# MagneticPowerSwitch.net
KiCad netlist of a schematic drawn in Altium Designer
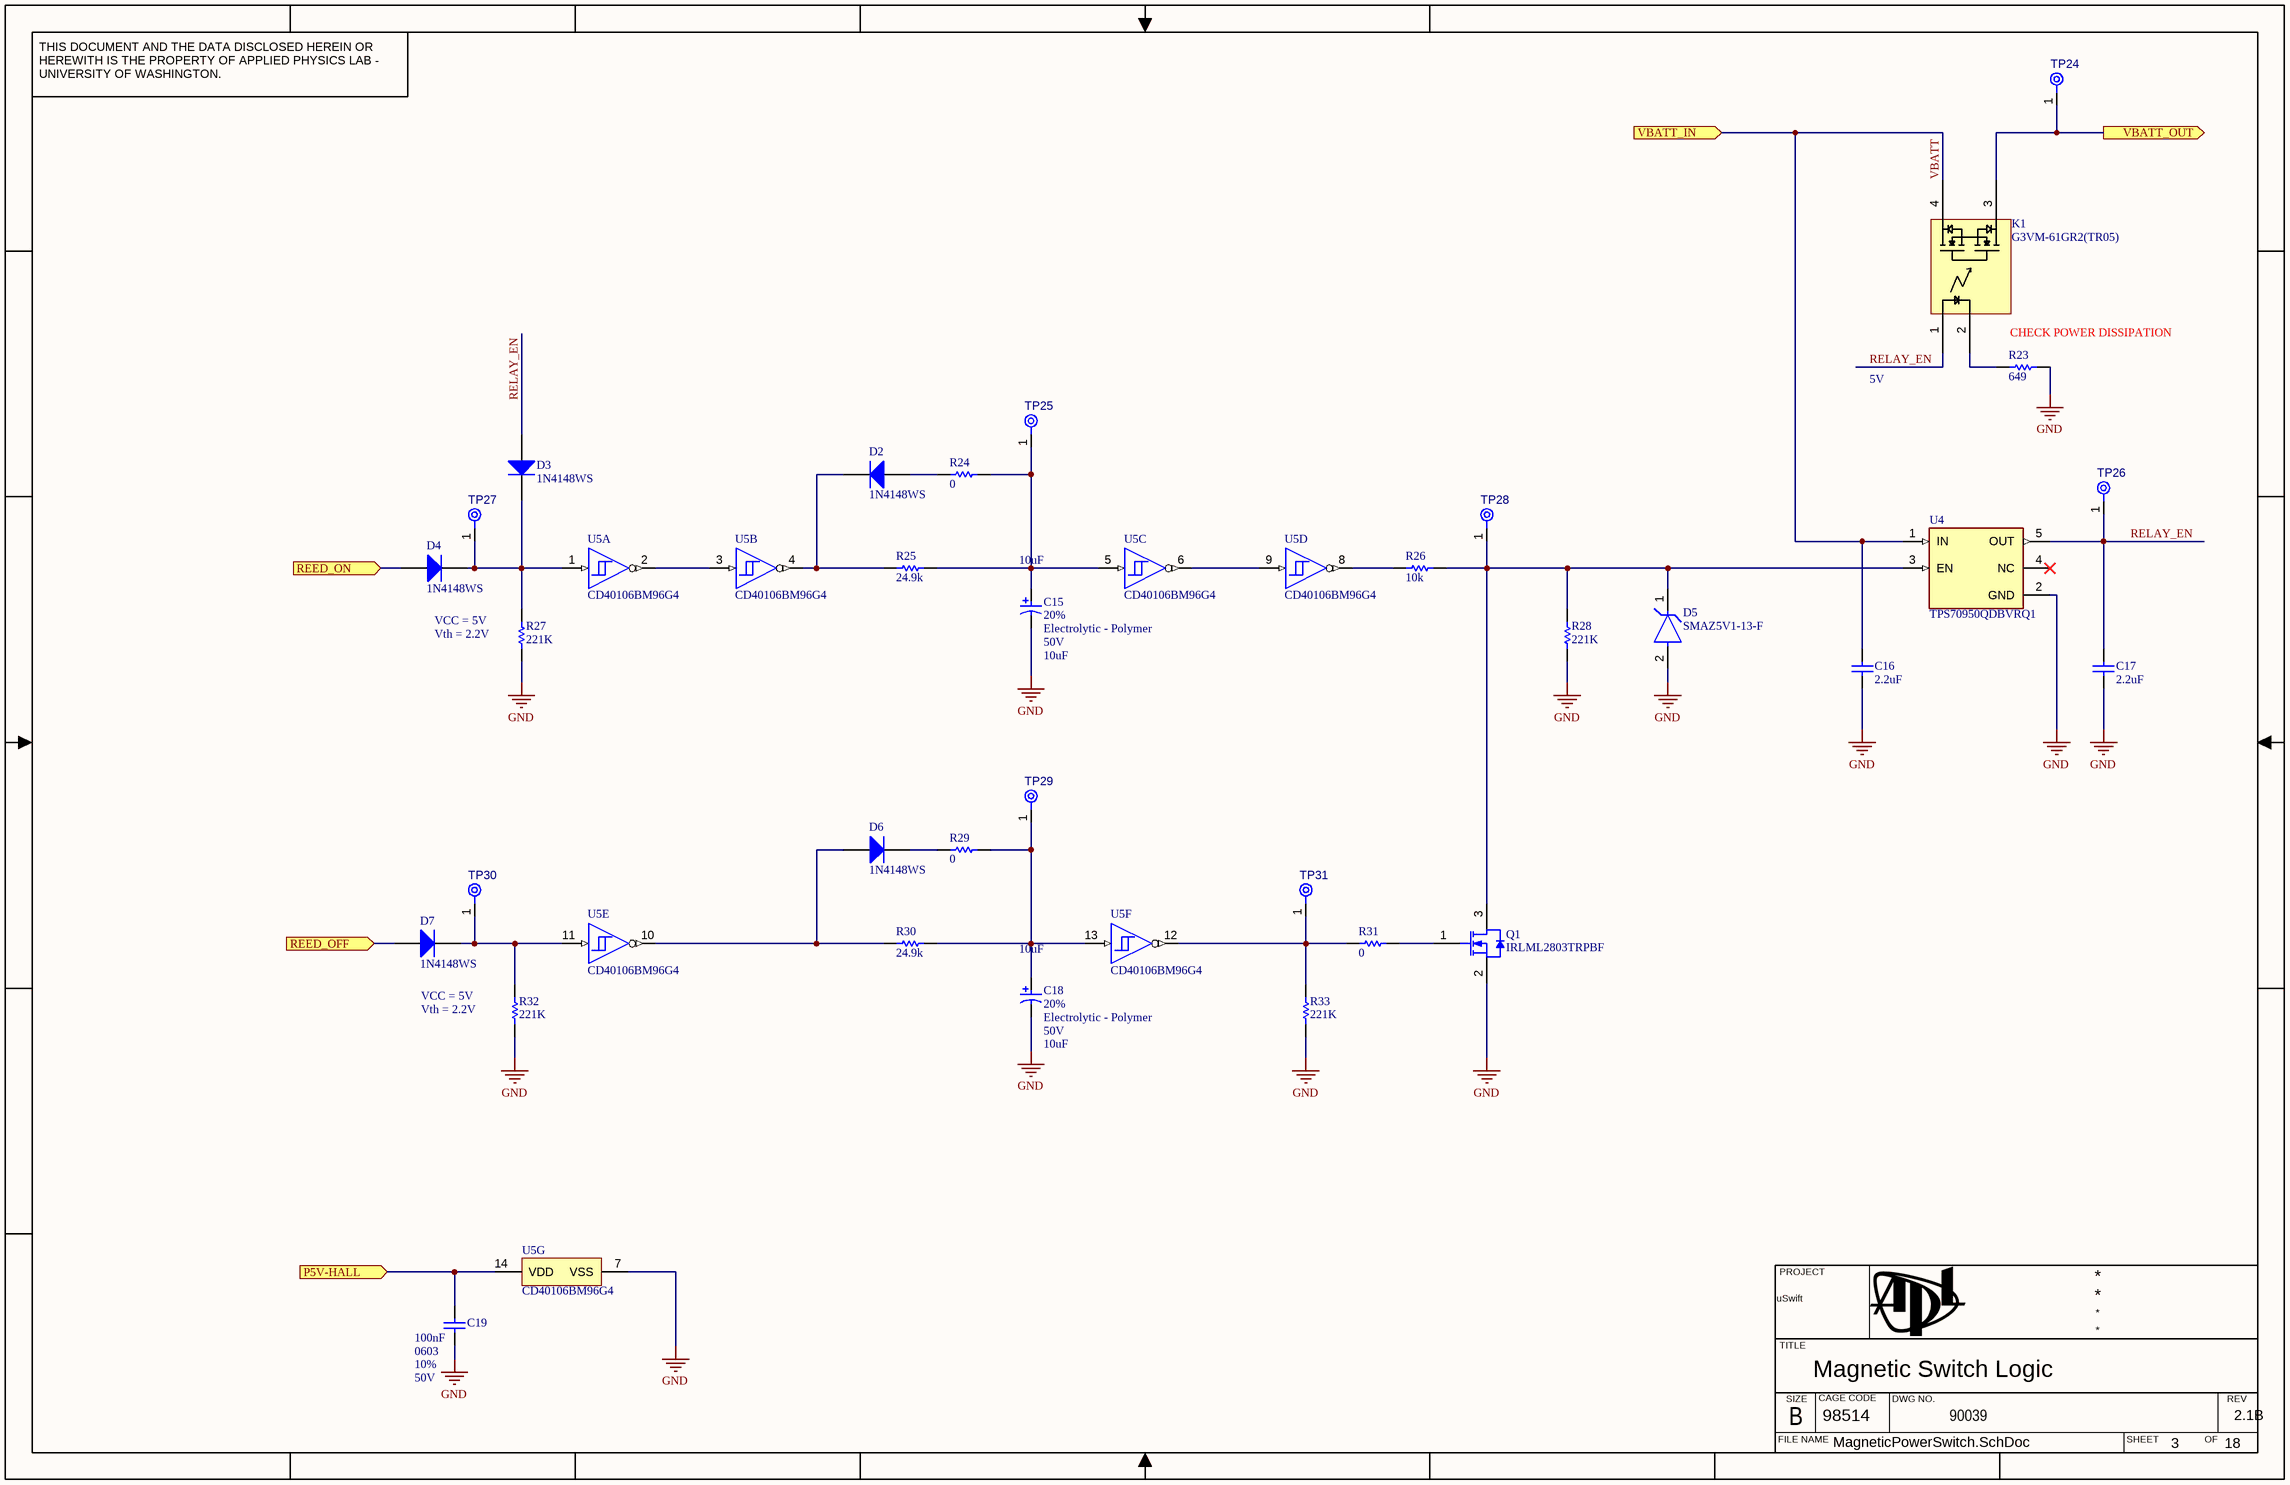
[diagram p0: MagneticPowerSwitch.SchDoc]

(export (version "E")
  (design (tool "Eeschema 10.0.6"))
  (components
    (comp (ref "C15")
      (value "10uF")
      (footprint "CAPAE5953X61M")
      (description "Cap Aluminum 10uF 50V 20% (5 X 5.8mm) SMD 0.12 Ohm 750mA 5000 hr 105°C Embossed T/R")
      (fields
        (field (name "TOLERANCE") "20%")
        (field (name "MATERIAL") "Electrolytic - Polymer")
        (field (name "MANUFACTURER") "Panasonic")
        (field (name "VOLTAGE RATING") "50V")
        (field (name "CAPACITANCE") "10uF")
        (field (name "PART NUMBER") "EEH-ZA1H100R")
      )
      (libsource (lib "Applied Physics Lab") (part "CAP-P-2"))
    )
    (comp (ref "C16")
      (value "2.2uF")
      (footprint "CAPC3225X270X30ML30")
      (description "Chip Capacitor, 2.2uF, 10%, 50 V, X7R 1210 (3225 Metric)")
      (fields (field (name "TOLERANCE") "10%") (field (name "Comment") "Capacitor 2.2uF 10%, 50V, X7R, 1210"))
      (libsource (lib "Applied Physics Lab") (part "CAP-NP-2"))
    )
    (comp (ref "C17")
      (value "2.2uF")
      (footprint "CAPC3225X270X30ML30")
      (description "Chip Capacitor, 2.2uF, 10%, 50 V, X7R 1210 (3225 Metric)")
      (fields (field (name "TOLERANCE") "10%") (field (name "Comment") "Capacitor 2.2uF 10%, 50V, X7R, 1210"))
      (libsource (lib "Applied Physics Lab") (part "CAP-NP-2"))
    )
    (comp (ref "C18")
      (value "10uF")
      (footprint "CAPAE5953X61M")
      (description "Cap Aluminum 10uF 50V 20% (5 X 5.8mm) SMD 0.12 Ohm 750mA 5000 hr 105°C Embossed T/R")
      (fields
        (field (name "TOLERANCE") "20%")
        (field (name "MATERIAL") "Electrolytic - Polymer")
        (field (name "MANUFACTURER") "Panasonic")
        (field (name "VOLTAGE RATING") "50V")
        (field (name "CAPACITANCE") "10uF")
        (field (name "PART NUMBER") "EEH-ZA1H100R")
      )
      (libsource (lib "Applied Physics Lab") (part "CAP-P-2"))
    )
    (comp (ref "C19")
      (value "100nF")
      (footprint "CAPC1608X90X40ML10T20")
      (description "Chip Capacitor, 100nF, +/- 10%, 50 V, X7R 0603 (1608 Metric)")
      (fields
        (field (name "CASE/PACKAGE") "0603")
        (field (name "TOLERANCE") "10%")
        (field (name "VOLTAGE RATING") "50V")
        (field (name "Comment") "Capacitor 100nF +/- 10%, 50V, X7R, 0603")
      )
      (libsource (lib "Applied Physics Lab") (part "CAP-NP-2"))
    )
    (comp (ref "D2")
      (value "1N4148WS")
      (footprint "FAIR-SOD-323_V")
      (description "Small Signal Diode, 75 V, 0.15 A, -55 to 150 degC, 2-Pin SOD-323, RoHS, Tape and Reel")
      (fields (field (name "MANUFACTURER") "Fairchild"))
      (libsource (lib "Applied Physics Lab") (part "D-AK-2"))
    )
    (comp (ref "D3")
      (value "1N4148WS")
      (footprint "FAIR-SOD-323_V")
      (description "Small Signal Diode, 75 V, 0.15 A, -55 to 150 degC, 2-Pin SOD-323, RoHS, Tape and Reel")
      (fields (field (name "MANUFACTURER") "Fairchild"))
      (libsource (lib "Applied Physics Lab") (part "D-AK-2"))
    )
    (comp (ref "D4")
      (value "1N4148WS")
      (footprint "FAIR-SOD-323_V")
      (description "Small Signal Diode, 75 V, 0.15 A, -55 to 150 degC, 2-Pin SOD-323, RoHS, Tape and Reel")
      (fields (field (name "MANUFACTURER") "Fairchild"))
      (libsource (lib "Applied Physics Lab") (part "D-AK-2"))
    )
    (comp (ref "D5")
      (value "SMAZ5V1-13-F")
      (footprint "FP-SMA-MFG")
      (description "Vz=5.1V 4.84V~5.4V Izt=100mA P=1W")
      (fields (field (name "TOLERANCE") "5%"))
      (libsource (lib "Applied Physics Lab") (part "f813f71cba58e380607f5dd3caf9714"))
    )
    (comp (ref "D6")
      (value "1N4148WS")
      (footprint "FAIR-SOD-323_V")
      (description "Small Signal Diode, 75 V, 0.15 A, -55 to 150 degC, 2-Pin SOD-323, RoHS, Tape and Reel")
      (fields (field (name "MANUFACTURER") "Fairchild"))
      (libsource (lib "Applied Physics Lab") (part "D-AK-2"))
    )
    (comp (ref "D7")
      (value "1N4148WS")
      (footprint "FAIR-SOD-323_V")
      (description "Small Signal Diode, 75 V, 0.15 A, -55 to 150 degC, 2-Pin SOD-323, RoHS, Tape and Reel")
      (fields (field (name "MANUFACTURER") "Fairchild"))
      (libsource (lib "Applied Physics Lab") (part "D-AK-2"))
    )
    (comp (ref "K1")
      (value "G3VM-61GR2(TR05)")
      (footprint "G3VM-61GR2(TR05)-Footprint-1")
      (description "Relay Ssr 25MA 1.48V Dc-in 1.3A 48V Ac/dc-out 4-PIN Sop T/r")
      (libsource (lib "Applied Physics Lab") (part "G3VM-Symbol-1"))
    )
    (comp (ref "Q1")
      (value "IRLML2803TRPBF")
      (footprint "SOT95P237X112-3M")
      (description "Mosfet, Power; N-ch; Vdss 30V; Rds(on) 0.25 Ohm; Id 1.2A; MICRO3; Pd 540MW; Vgs +/-20V")
      (fields (field (name "MANUFACTURER") "International Rectifier"))
      (libsource (lib "Applied Physics Lab") (part "NEMOS-GSD-3"))
    )
    (comp (ref "R23")
      (value "649")
      (footprint "RESC1609X50X30ML08T20")
      (description "Chip Resistor, 649 Ohm, +/- 1%, 0.1 W, -55 to 155 degC, 0603 (1608 Metric)")
      (fields (field (name "POWER") "100mW") (field (name "TOLERANCE") "1%"))
      (libsource (lib "Applied Physics Lab") (part "RES-2"))
    )
    (comp (ref "R24")
      (value "0")
      (footprint "RESC1608X55X25ML10T15")
      (description "Chip Resistor, 0 Ohm, 0.1 W, -55 to 155 degC, 0603 (1608 Metric)")
      (fields (field (name "TOLERANCE") "5%") (field (name "POWER") "100mW"))
      (libsource (lib "Applied Physics Lab") (part "RES-2"))
    )
    (comp (ref "R25")
      (value "24.9k")
      (footprint "RESC1608X55X25ML10T15")
      (description "Chip Resistor, 24.9k Ohm, +/- 1%, 0.1 W, -55 to 155 degC, 0603 (1608 Metric)")
      (fields (field (name "TOLERANCE") "1%") (field (name "POWER") "100mW"))
      (libsource (lib "Applied Physics Lab") (part "RES-2"))
    )
    (comp (ref "R26")
      (value "10k")
      (footprint "RESC1608X55X25ML10T15")
      (description "Chip Resistor, 10 KOhm, +/- 1%, 01 W, -55 to 155 degC, 0603 (1608 Metric)")
      (fields (field (name "TOLERANCE") "1%") (field (name "POWER") "100mW"))
      (libsource (lib "Applied Physics Lab") (part "RES-2"))
    )
    (comp (ref "R27")
      (value "221K")
      (footprint "RESC1609X50X30ML08T20")
      (description "Chip Resistor, 221k Ohm, +/- 1%, 0.1 W, -55 to 155 degC, 0603 (1608 Metric)")
      (fields (field (name "TOLERANCE") "1%") (field (name "POWER") "100mW"))
      (libsource (lib "Applied Physics Lab") (part "RES-2"))
    )
    (comp (ref "R28")
      (value "221K")
      (footprint "RESC1609X50X30ML08T20")
      (description "Chip Resistor, 221k Ohm, +/- 1%, 0.1 W, -55 to 155 degC, 0603 (1608 Metric)")
      (fields (field (name "TOLERANCE") "1%") (field (name "POWER") "100mW"))
      (libsource (lib "Applied Physics Lab") (part "RES-2"))
    )
    (comp (ref "R29")
      (value "0")
      (footprint "RESC1608X55X25ML10T15")
      (description "Chip Resistor, 0 Ohm, 0.1 W, -55 to 155 degC, 0603 (1608 Metric)")
      (fields (field (name "TOLERANCE") "5%") (field (name "POWER") "100mW"))
      (libsource (lib "Applied Physics Lab") (part "RES-2"))
    )
    (comp (ref "R30")
      (value "24.9k")
      (footprint "RESC1608X55X25ML10T15")
      (description "Chip Resistor, 24.9k Ohm, +/- 1%, 0.1 W, -55 to 155 degC, 0603 (1608 Metric)")
      (fields (field (name "TOLERANCE") "1%") (field (name "POWER") "100mW"))
      (libsource (lib "Applied Physics Lab") (part "RES-2"))
    )
    (comp (ref "R31")
      (value "0")
      (footprint "RESC1608X55X25ML10T15")
      (description "Chip Resistor, 0 Ohm, 0.1 W, -55 to 155 degC, 0603 (1608 Metric)")
      (fields (field (name "TOLERANCE") "5%") (field (name "POWER") "100mW"))
      (libsource (lib "Applied Physics Lab") (part "RES-2"))
    )
    (comp (ref "R32")
      (value "221K")
      (footprint "RESC1609X50X30ML08T20")
      (description "Chip Resistor, 221k Ohm, +/- 1%, 0.1 W, -55 to 155 degC, 0603 (1608 Metric)")
      (fields (field (name "TOLERANCE") "1%") (field (name "POWER") "100mW"))
      (libsource (lib "Applied Physics Lab") (part "RES-2"))
    )
    (comp (ref "R33")
      (value "221K")
      (footprint "RESC1609X50X30ML08T20")
      (description "Chip Resistor, 221k Ohm, +/- 1%, 0.1 W, -55 to 155 degC, 0603 (1608 Metric)")
      (fields (field (name "TOLERANCE") "1%") (field (name "POWER") "100mW"))
      (libsource (lib "Applied Physics Lab") (part "RES-2"))
    )
    (comp (ref "TP24")
      (value "TPAD6R-CIRCLED")
      (footprint "TP06R - Circled")
      (description "0.6mm round with a silkscreen circle.")
      (libsource (lib "Applied Physics Lab") (part "CMP-001-0001-4"))
    )
    (comp (ref "TP25")
      (value "TPAD6R-CIRCLED")
      (footprint "TP06R - Circled")
      (description "0.6mm round with a silkscreen circle.")
      (libsource (lib "Applied Physics Lab") (part "CMP-001-0001-4"))
    )
    (comp (ref "TP26")
      (value "TPAD6R-CIRCLED")
      (footprint "TP06R - Circled")
      (description "0.6mm round with a silkscreen circle.")
      (libsource (lib "Applied Physics Lab") (part "CMP-001-0001-4"))
    )
    (comp (ref "TP27")
      (value "TPAD6R-CIRCLED")
      (footprint "TP06R - Circled")
      (description "0.6mm round with a silkscreen circle.")
      (libsource (lib "Applied Physics Lab") (part "CMP-001-0001-4"))
    )
    (comp (ref "TP28")
      (value "TPAD6R-CIRCLED")
      (footprint "TP06R - Circled")
      (description "0.6mm round with a silkscreen circle.")
      (libsource (lib "Applied Physics Lab") (part "CMP-001-0001-4"))
    )
    (comp (ref "TP29")
      (value "TPAD6R-CIRCLED")
      (footprint "TP06R - Circled")
      (description "0.6mm round with a silkscreen circle.")
      (libsource (lib "Applied Physics Lab") (part "CMP-001-0001-4"))
    )
    (comp (ref "TP30")
      (value "TPAD6R-CIRCLED")
      (footprint "TP06R - Circled")
      (description "0.6mm round with a silkscreen circle.")
      (libsource (lib "Applied Physics Lab") (part "CMP-001-0001-4"))
    )
    (comp (ref "TP31")
      (value "TPAD6R-CIRCLED")
      (footprint "TP06R - Circled")
      (description "0.6mm round with a silkscreen circle.")
      (libsource (lib "Applied Physics Lab") (part "CMP-001-0001-4"))
    )
    (comp (ref "U4")
      (value "TPS70950QDBVRQ1")
      (footprint "FP-DBV0005A-IPC_A")
      (description "LDO Regulator Pos 5V 0.15A 5-Pin SOT-23 T/R")
      (libsource (lib "Applied Physics Lab") (part "030fc2a58bb2cf79005932a3da0ea32"))
    )
    (comp (ref "U5")
      (value "CD40106BM96G4")
      (footprint "D0014A_M")
      (description "6-ch, 3-V to 18-V inverters with Schmitt-Trigger inputs 14-SOIC -55 to 125")
      (libsource (lib "Applied Physics Lab") (part "TI-CD40XXXB-14-SCHMITT"))
    )
  )
  (nets
    (net (code "1") (name "/P5V-HALL") (class "Default")
      (node (ref "C19") (pin "2") (pinfunction "2_2") (pintype "passive"))
      (node (ref "U5") (pin "14") (pinfunction "VDD_14") (pintype "power_in"))
    )
    (net (code "2") (name "/REED_OFF") (class "Default")
      (node (ref "D7") (pin "1") (pinfunction "A_1") (pintype "passive"))
    )
    (net (code "3") (name "/REED_ON") (class "Default")
      (node (ref "D4") (pin "1") (pinfunction "A_1") (pintype "passive"))
    )
    (net (code "4") (name "/RELAY_EN") (class "Default")
      (node (ref "C17") (pin "2") (pinfunction "2_2") (pintype "passive"))
      (node (ref "D3") (pin "1") (pinfunction "A_1") (pintype "passive"))
      (node (ref "K1") (pin "1") (pinfunction "+_CNTL_1") (pintype "passive"))
      (node (ref "TP26") (pin "1") (pinfunction "TP_1") (pintype "passive"))
      (node (ref "U4") (pin "5") (pinfunction "OUT_5") (pintype "output"))
    )
    (net (code "5") (name "/VBATT") (class "Default")
      (node (ref "C16") (pin "2") (pinfunction "2_2") (pintype "passive"))
      (node (ref "K1") (pin "4") (pinfunction "DRAIN_4") (pintype "passive"))
      (node (ref "U4") (pin "1") (pinfunction "IN_1") (pintype "input"))
    )
    (net (code "6") (name "/VBATT_OUT") (class "Default")
      (node (ref "K1") (pin "3") (pinfunction "DRAIN_3") (pintype "passive"))
      (node (ref "TP24") (pin "1") (pinfunction "TP_1") (pintype "passive"))
    )
    (net (code "7") (name "GND") (class "Default")
      (node (ref "C15") (pin "2") (pinfunction "2_2") (pintype "passive"))
      (node (ref "C16") (pin "1") (pinfunction "1_1") (pintype "passive"))
      (node (ref "C17") (pin "1") (pinfunction "1_1") (pintype "passive"))
      (node (ref "C18") (pin "2") (pinfunction "2_2") (pintype "passive"))
      (node (ref "C19") (pin "1") (pinfunction "1_1") (pintype "passive"))
      (node (ref "D5") (pin "2") (pinfunction "A_2") (pintype "passive"))
      (node (ref "Q1") (pin "2") (pinfunction "S_2") (pintype "passive"))
      (node (ref "R23") (pin "1") (pinfunction "1_1") (pintype "passive"))
      (node (ref "R27") (pin "1") (pinfunction "1_1") (pintype "passive"))
      (node (ref "R28") (pin "1") (pinfunction "1_1") (pintype "passive"))
      (node (ref "R32") (pin "1") (pinfunction "1_1") (pintype "passive"))
      (node (ref "R33") (pin "1") (pinfunction "1_1") (pintype "passive"))
      (node (ref "U4") (pin "2") (pinfunction "GND_2") (pintype "power_in"))
      (node (ref "U5") (pin "7") (pinfunction "VSS_7") (pintype "power_in"))
    )
    (net (code "8") (name "Net-(D2-A)") (class "Default")
      (node (ref "D2") (pin "1") (pinfunction "A_1") (pintype "passive"))
      (node (ref "R24") (pin "1") (pinfunction "1_1") (pintype "passive"))
    )
    (net (code "9") (name "Net-(D2-K)") (class "Default")
      (node (ref "D2") (pin "2") (pinfunction "K_2") (pintype "passive"))
      (node (ref "R25") (pin "1") (pinfunction "1_1") (pintype "passive"))
      (node (ref "U5") (pin "4") (pinfunction "H=~{B}_4") (pintype "output"))
    )
    (net (code "10") (name "Net-(D3-K)") (class "Default")
      (node (ref "D3") (pin "2") (pinfunction "K_2") (pintype "passive"))
      (node (ref "D4") (pin "2") (pinfunction "K_2") (pintype "passive"))
      (node (ref "R27") (pin "2") (pinfunction "2_2") (pintype "passive"))
      (node (ref "TP27") (pin "1") (pinfunction "TP_1") (pintype "passive"))
      (node (ref "U5") (pin "1") (pinfunction "A_1") (pintype "input"))
    )
    (net (code "11") (name "Net-(D5-C)") (class "Default")
      (node (ref "D5") (pin "1") (pinfunction "C_1") (pintype "passive"))
      (node (ref "Q1") (pin "3") (pinfunction "D_3") (pintype "passive"))
      (node (ref "R26") (pin "2") (pinfunction "2_2") (pintype "passive"))
      (node (ref "R28") (pin "2") (pinfunction "2_2") (pintype "passive"))
      (node (ref "TP28") (pin "1") (pinfunction "TP_1") (pintype "passive"))
      (node (ref "U4") (pin "3") (pinfunction "EN_3") (pintype "input"))
    )
    (net (code "12") (name "Net-(D6-A)") (class "Default")
      (node (ref "D6") (pin "1") (pinfunction "A_1") (pintype "passive"))
      (node (ref "R30") (pin "1") (pinfunction "1_1") (pintype "passive"))
      (node (ref "U5") (pin "10") (pinfunction "K=~{E}_10") (pintype "output"))
    )
    (net (code "13") (name "Net-(D6-K)") (class "Default")
      (node (ref "D6") (pin "2") (pinfunction "K_2") (pintype "passive"))
      (node (ref "R29") (pin "1") (pinfunction "1_1") (pintype "passive"))
    )
    (net (code "14") (name "Net-(D7-K)") (class "Default")
      (node (ref "D7") (pin "2") (pinfunction "K_2") (pintype "passive"))
      (node (ref "R32") (pin "2") (pinfunction "2_2") (pintype "passive"))
      (node (ref "TP30") (pin "1") (pinfunction "TP_1") (pintype "passive"))
      (node (ref "U5") (pin "11") (pinfunction "E_11") (pintype "input"))
    )
    (net (code "15") (name "Net-(K1--_CNTL)") (class "Default")
      (node (ref "K1") (pin "2") (pinfunction "-_CNTL_2") (pintype "passive"))
      (node (ref "R23") (pin "2") (pinfunction "2_2") (pintype "passive"))
    )
    (net (code "16") (name "Net-(Q1-G)") (class "Default")
      (node (ref "Q1") (pin "1") (pinfunction "G_1") (pintype "passive"))
      (node (ref "R31") (pin "2") (pinfunction "2_2") (pintype "passive"))
    )
    (net (code "17") (name "Net-(TP25-TP)") (class "Default")
      (node (ref "C15") (pin "1") (pinfunction "1_1") (pintype "passive"))
      (node (ref "R24") (pin "2") (pinfunction "2_2") (pintype "passive"))
      (node (ref "R25") (pin "2") (pinfunction "2_2") (pintype "passive"))
      (node (ref "TP25") (pin "1") (pinfunction "TP_1") (pintype "passive"))
      (node (ref "U5") (pin "5") (pinfunction "C_5") (pintype "input"))
    )
    (net (code "18") (name "Net-(TP29-TP)") (class "Default")
      (node (ref "C18") (pin "1") (pinfunction "1_1") (pintype "passive"))
      (node (ref "R29") (pin "2") (pinfunction "2_2") (pintype "passive"))
      (node (ref "R30") (pin "2") (pinfunction "2_2") (pintype "passive"))
      (node (ref "TP29") (pin "1") (pinfunction "TP_1") (pintype "passive"))
      (node (ref "U5") (pin "13") (pinfunction "F_13") (pintype "input"))
    )
    (net (code "19") (name "Net-(TP31-TP)") (class "Default")
      (node (ref "R31") (pin "1") (pinfunction "1_1") (pintype "passive"))
      (node (ref "R33") (pin "2") (pinfunction "2_2") (pintype "passive"))
      (node (ref "TP31") (pin "1") (pinfunction "TP_1") (pintype "passive"))
      (node (ref "U5") (pin "12") (pinfunction "L=~{F}_12") (pintype "output"))
    )
    (net (code "20") (name "Net-(U5A-G=~{A})") (class "Default")
      (node (ref "U5") (pin "2") (pinfunction "G=~{A}_2") (pintype "output"))
      (node (ref "U5") (pin "3") (pinfunction "B_3") (pintype "input"))
    )
    (net (code "21") (name "Net-(U5C-I=~{C})") (class "Default")
      (node (ref "U5") (pin "6") (pinfunction "I=~{C}_6") (pintype "output"))
      (node (ref "U5") (pin "9") (pinfunction "D_9") (pintype "input"))
    )
    (net (code "22") (name "Net-(U5D-J=~{D})") (class "Default")
      (node (ref "R26") (pin "1") (pinfunction "1_1") (pintype "passive"))
      (node (ref "U5") (pin "8") (pinfunction "J=~{D}_8") (pintype "output"))
    )
    (net (code "23") (name "unconnected-(U4-NC-Pad4)") (class "Default")
      (node (ref "U4") (pin "4") (pinfunction "NC_4") (pintype "passive+no_connect"))
    )
  )
)
